# LED_Driver_and_LEDs_03.net
KiCad netlist of a schematic drawn in Altium Designer
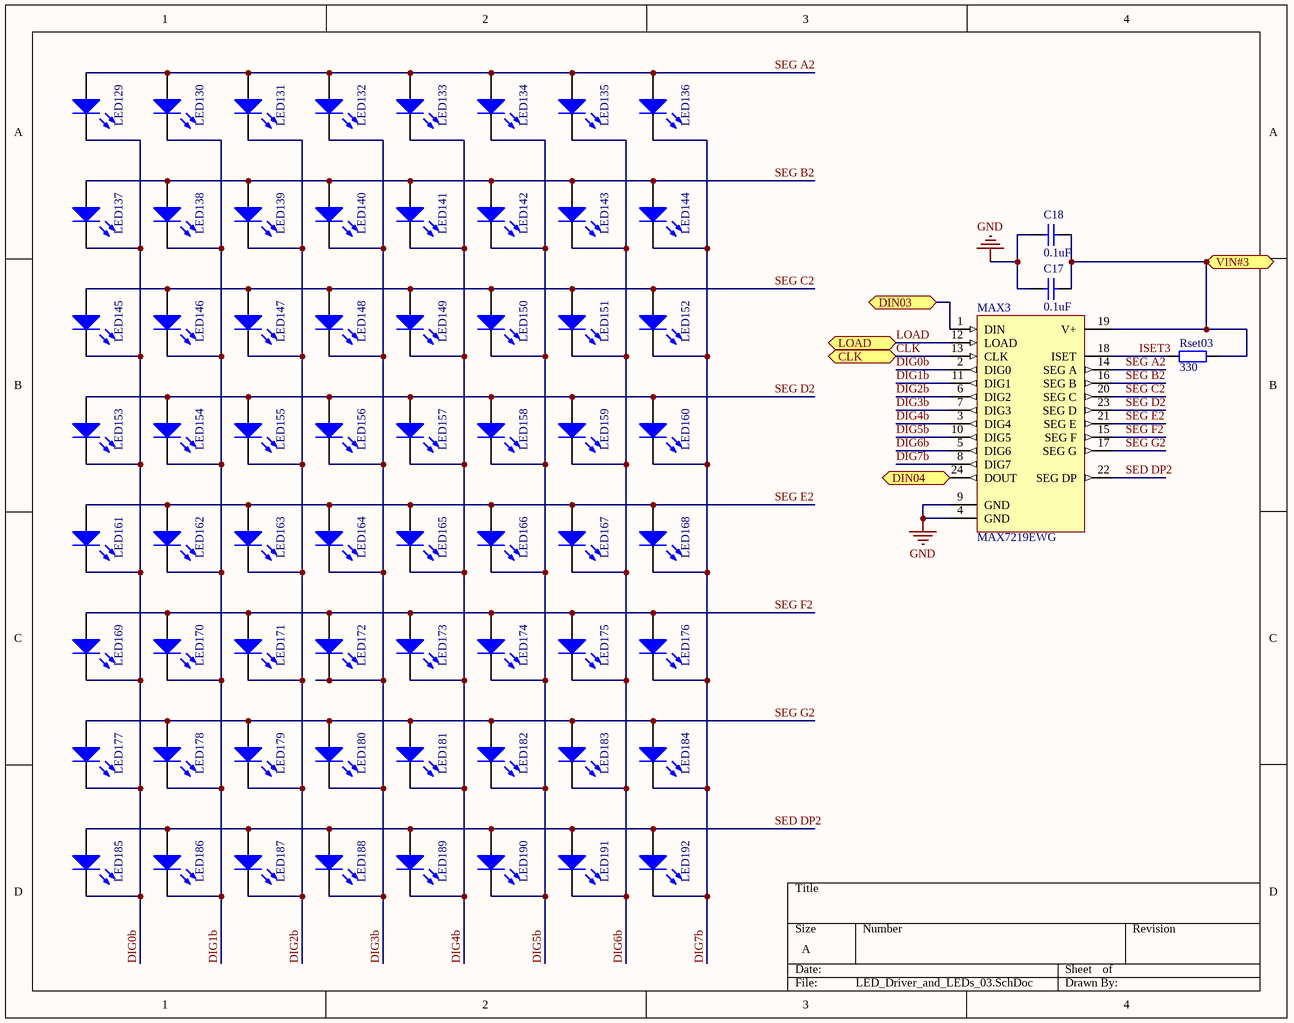
[diagram p0: LED_Driver_and_LEDs_03.SchDoc]

(export (version "E")
  (design (tool "Eeschema 10.0.6"))
  (components
    (comp (ref "C17")
      (value "0.1uF")
      (footprint "6-0805_N")
      (description "Capacitor (Semiconductor SIM Model)")
      (fields (field (name "Comment") "Cap Semi") (field (name "PUBLISHER") "Altium Limited"))
      (libsource (lib "Miscellaneous Devices") (part "Cap Semi"))
    )
    (comp (ref "C18")
      (value "0.1uF")
      (footprint "6-0805_N")
      (description "Capacitor (Semiconductor SIM Model)")
      (fields (field (name "Comment") "Cap Semi") (field (name "PUBLISHER") "Altium Limited"))
      (libsource (lib "Miscellaneous Devices") (part "Cap Semi"))
    )
    (comp (ref "LED129")
      (value "LED3")
      (footprint "3.5X2.8X1.9")
      (description "Typical BLUE SiC LED")
      (fields (field (name "PUBLISHER") "Altium Limited"))
      (libsource (lib "Miscellaneous Devices") (part "LED3"))
    )
    (comp (ref "LED130")
      (value "LED3")
      (footprint "3.5X2.8X1.9")
      (description "Typical BLUE SiC LED")
      (fields (field (name "PUBLISHER") "Altium Limited"))
      (libsource (lib "Miscellaneous Devices") (part "LED3"))
    )
    (comp (ref "LED131")
      (value "LED3")
      (footprint "3.5X2.8X1.9")
      (description "Typical BLUE SiC LED")
      (fields (field (name "PUBLISHER") "Altium Limited"))
      (libsource (lib "Miscellaneous Devices") (part "LED3"))
    )
    (comp (ref "LED132")
      (value "LED3")
      (footprint "3.5X2.8X1.9")
      (description "Typical BLUE SiC LED")
      (fields (field (name "PUBLISHER") "Altium Limited"))
      (libsource (lib "Miscellaneous Devices") (part "LED3"))
    )
    (comp (ref "LED133")
      (value "LED3")
      (footprint "3.5X2.8X1.9")
      (description "Typical BLUE SiC LED")
      (fields (field (name "PUBLISHER") "Altium Limited"))
      (libsource (lib "Miscellaneous Devices") (part "LED3"))
    )
    (comp (ref "LED134")
      (value "LED3")
      (footprint "3.5X2.8X1.9")
      (description "Typical BLUE SiC LED")
      (fields (field (name "PUBLISHER") "Altium Limited"))
      (libsource (lib "Miscellaneous Devices") (part "LED3"))
    )
    (comp (ref "LED135")
      (value "LED3")
      (footprint "3.5X2.8X1.9")
      (description "Typical BLUE SiC LED")
      (fields (field (name "PUBLISHER") "Altium Limited"))
      (libsource (lib "Miscellaneous Devices") (part "LED3"))
    )
    (comp (ref "LED136")
      (value "LED3")
      (footprint "3.5X2.8X1.9")
      (description "Typical BLUE SiC LED")
      (fields (field (name "PUBLISHER") "Altium Limited"))
      (libsource (lib "Miscellaneous Devices") (part "LED3"))
    )
    (comp (ref "LED137")
      (value "LED3")
      (footprint "3.5X2.8X1.9")
      (description "Typical BLUE SiC LED")
      (fields (field (name "PUBLISHER") "Altium Limited"))
      (libsource (lib "Miscellaneous Devices") (part "LED3"))
    )
    (comp (ref "LED138")
      (value "LED3")
      (footprint "3.5X2.8X1.9")
      (description "Typical BLUE SiC LED")
      (fields (field (name "PUBLISHER") "Altium Limited"))
      (libsource (lib "Miscellaneous Devices") (part "LED3"))
    )
    (comp (ref "LED139")
      (value "LED3")
      (footprint "3.5X2.8X1.9")
      (description "Typical BLUE SiC LED")
      (fields (field (name "PUBLISHER") "Altium Limited"))
      (libsource (lib "Miscellaneous Devices") (part "LED3"))
    )
    (comp (ref "LED140")
      (value "LED3")
      (footprint "3.5X2.8X1.9")
      (description "Typical BLUE SiC LED")
      (fields (field (name "PUBLISHER") "Altium Limited"))
      (libsource (lib "Miscellaneous Devices") (part "LED3"))
    )
    (comp (ref "LED141")
      (value "LED3")
      (footprint "3.5X2.8X1.9")
      (description "Typical BLUE SiC LED")
      (fields (field (name "PUBLISHER") "Altium Limited"))
      (libsource (lib "Miscellaneous Devices") (part "LED3"))
    )
    (comp (ref "LED142")
      (value "LED3")
      (footprint "3.5X2.8X1.9")
      (description "Typical BLUE SiC LED")
      (fields (field (name "PUBLISHER") "Altium Limited"))
      (libsource (lib "Miscellaneous Devices") (part "LED3"))
    )
    (comp (ref "LED143")
      (value "LED3")
      (footprint "3.5X2.8X1.9")
      (description "Typical BLUE SiC LED")
      (fields (field (name "PUBLISHER") "Altium Limited"))
      (libsource (lib "Miscellaneous Devices") (part "LED3"))
    )
    (comp (ref "LED144")
      (value "LED3")
      (footprint "3.5X2.8X1.9")
      (description "Typical BLUE SiC LED")
      (fields (field (name "PUBLISHER") "Altium Limited"))
      (libsource (lib "Miscellaneous Devices") (part "LED3"))
    )
    (comp (ref "LED145")
      (value "LED3")
      (footprint "3.5X2.8X1.9")
      (description "Typical BLUE SiC LED")
      (fields (field (name "PUBLISHER") "Altium Limited"))
      (libsource (lib "Miscellaneous Devices") (part "LED3"))
    )
    (comp (ref "LED146")
      (value "LED3")
      (footprint "3.5X2.8X1.9")
      (description "Typical BLUE SiC LED")
      (fields (field (name "PUBLISHER") "Altium Limited"))
      (libsource (lib "Miscellaneous Devices") (part "LED3"))
    )
    (comp (ref "LED147")
      (value "LED3")
      (footprint "3.5X2.8X1.9")
      (description "Typical BLUE SiC LED")
      (fields (field (name "PUBLISHER") "Altium Limited"))
      (libsource (lib "Miscellaneous Devices") (part "LED3"))
    )
    (comp (ref "LED148")
      (value "LED3")
      (footprint "3.5X2.8X1.9")
      (description "Typical BLUE SiC LED")
      (fields (field (name "PUBLISHER") "Altium Limited"))
      (libsource (lib "Miscellaneous Devices") (part "LED3"))
    )
    (comp (ref "LED149")
      (value "LED3")
      (footprint "3.5X2.8X1.9")
      (description "Typical BLUE SiC LED")
      (fields (field (name "PUBLISHER") "Altium Limited"))
      (libsource (lib "Miscellaneous Devices") (part "LED3"))
    )
    (comp (ref "LED150")
      (value "LED3")
      (footprint "3.5X2.8X1.9")
      (description "Typical BLUE SiC LED")
      (fields (field (name "PUBLISHER") "Altium Limited"))
      (libsource (lib "Miscellaneous Devices") (part "LED3"))
    )
    (comp (ref "LED151")
      (value "LED3")
      (footprint "3.5X2.8X1.9")
      (description "Typical BLUE SiC LED")
      (fields (field (name "PUBLISHER") "Altium Limited"))
      (libsource (lib "Miscellaneous Devices") (part "LED3"))
    )
    (comp (ref "LED152")
      (value "LED3")
      (footprint "3.5X2.8X1.9")
      (description "Typical BLUE SiC LED")
      (fields (field (name "PUBLISHER") "Altium Limited"))
      (libsource (lib "Miscellaneous Devices") (part "LED3"))
    )
    (comp (ref "LED153")
      (value "LED3")
      (footprint "3.5X2.8X1.9")
      (description "Typical BLUE SiC LED")
      (fields (field (name "PUBLISHER") "Altium Limited"))
      (libsource (lib "Miscellaneous Devices") (part "LED3"))
    )
    (comp (ref "LED154")
      (value "LED3")
      (footprint "3.5X2.8X1.9")
      (description "Typical BLUE SiC LED")
      (fields (field (name "PUBLISHER") "Altium Limited"))
      (libsource (lib "Miscellaneous Devices") (part "LED3"))
    )
    (comp (ref "LED155")
      (value "LED3")
      (footprint "3.5X2.8X1.9")
      (description "Typical BLUE SiC LED")
      (fields (field (name "PUBLISHER") "Altium Limited"))
      (libsource (lib "Miscellaneous Devices") (part "LED3"))
    )
    (comp (ref "LED156")
      (value "LED3")
      (footprint "3.5X2.8X1.9")
      (description "Typical BLUE SiC LED")
      (fields (field (name "PUBLISHER") "Altium Limited"))
      (libsource (lib "Miscellaneous Devices") (part "LED3"))
    )
    (comp (ref "LED157")
      (value "LED3")
      (footprint "3.5X2.8X1.9")
      (description "Typical BLUE SiC LED")
      (fields (field (name "PUBLISHER") "Altium Limited"))
      (libsource (lib "Miscellaneous Devices") (part "LED3"))
    )
    (comp (ref "LED158")
      (value "LED3")
      (footprint "3.5X2.8X1.9")
      (description "Typical BLUE SiC LED")
      (fields (field (name "PUBLISHER") "Altium Limited"))
      (libsource (lib "Miscellaneous Devices") (part "LED3"))
    )
    (comp (ref "LED159")
      (value "LED3")
      (footprint "3.5X2.8X1.9")
      (description "Typical BLUE SiC LED")
      (fields (field (name "PUBLISHER") "Altium Limited"))
      (libsource (lib "Miscellaneous Devices") (part "LED3"))
    )
    (comp (ref "LED160")
      (value "LED3")
      (footprint "3.5X2.8X1.9")
      (description "Typical BLUE SiC LED")
      (fields (field (name "PUBLISHER") "Altium Limited"))
      (libsource (lib "Miscellaneous Devices") (part "LED3"))
    )
    (comp (ref "LED161")
      (value "LED3")
      (footprint "3.5X2.8X1.9")
      (description "Typical BLUE SiC LED")
      (fields (field (name "PUBLISHER") "Altium Limited"))
      (libsource (lib "Miscellaneous Devices") (part "LED3"))
    )
    (comp (ref "LED162")
      (value "LED3")
      (footprint "3.5X2.8X1.9")
      (description "Typical BLUE SiC LED")
      (fields (field (name "PUBLISHER") "Altium Limited"))
      (libsource (lib "Miscellaneous Devices") (part "LED3"))
    )
    (comp (ref "LED163")
      (value "LED3")
      (footprint "3.5X2.8X1.9")
      (description "Typical BLUE SiC LED")
      (fields (field (name "PUBLISHER") "Altium Limited"))
      (libsource (lib "Miscellaneous Devices") (part "LED3"))
    )
    (comp (ref "LED164")
      (value "LED3")
      (footprint "3.5X2.8X1.9")
      (description "Typical BLUE SiC LED")
      (fields (field (name "PUBLISHER") "Altium Limited"))
      (libsource (lib "Miscellaneous Devices") (part "LED3"))
    )
    (comp (ref "LED165")
      (value "LED3")
      (footprint "3.5X2.8X1.9")
      (description "Typical BLUE SiC LED")
      (fields (field (name "PUBLISHER") "Altium Limited"))
      (libsource (lib "Miscellaneous Devices") (part "LED3"))
    )
    (comp (ref "LED166")
      (value "LED3")
      (footprint "3.5X2.8X1.9")
      (description "Typical BLUE SiC LED")
      (fields (field (name "PUBLISHER") "Altium Limited"))
      (libsource (lib "Miscellaneous Devices") (part "LED3"))
    )
    (comp (ref "LED167")
      (value "LED3")
      (footprint "3.5X2.8X1.9")
      (description "Typical BLUE SiC LED")
      (fields (field (name "PUBLISHER") "Altium Limited"))
      (libsource (lib "Miscellaneous Devices") (part "LED3"))
    )
    (comp (ref "LED168")
      (value "LED3")
      (footprint "3.5X2.8X1.9")
      (description "Typical BLUE SiC LED")
      (fields (field (name "PUBLISHER") "Altium Limited"))
      (libsource (lib "Miscellaneous Devices") (part "LED3"))
    )
    (comp (ref "LED169")
      (value "LED3")
      (footprint "3.5X2.8X1.9")
      (description "Typical BLUE SiC LED")
      (fields (field (name "PUBLISHER") "Altium Limited"))
      (libsource (lib "Miscellaneous Devices") (part "LED3"))
    )
    (comp (ref "LED170")
      (value "LED3")
      (footprint "3.5X2.8X1.9")
      (description "Typical BLUE SiC LED")
      (fields (field (name "PUBLISHER") "Altium Limited"))
      (libsource (lib "Miscellaneous Devices") (part "LED3"))
    )
    (comp (ref "LED171")
      (value "LED3")
      (footprint "3.5X2.8X1.9")
      (description "Typical BLUE SiC LED")
      (fields (field (name "PUBLISHER") "Altium Limited"))
      (libsource (lib "Miscellaneous Devices") (part "LED3"))
    )
    (comp (ref "LED172")
      (value "LED3")
      (footprint "3.5X2.8X1.9")
      (description "Typical BLUE SiC LED")
      (fields (field (name "PUBLISHER") "Altium Limited"))
      (libsource (lib "Miscellaneous Devices") (part "LED3"))
    )
    (comp (ref "LED173")
      (value "LED3")
      (footprint "3.5X2.8X1.9")
      (description "Typical BLUE SiC LED")
      (fields (field (name "PUBLISHER") "Altium Limited"))
      (libsource (lib "Miscellaneous Devices") (part "LED3"))
    )
    (comp (ref "LED174")
      (value "LED3")
      (footprint "3.5X2.8X1.9")
      (description "Typical BLUE SiC LED")
      (fields (field (name "PUBLISHER") "Altium Limited"))
      (libsource (lib "Miscellaneous Devices") (part "LED3"))
    )
    (comp (ref "LED175")
      (value "LED3")
      (footprint "3.5X2.8X1.9")
      (description "Typical BLUE SiC LED")
      (fields (field (name "PUBLISHER") "Altium Limited"))
      (libsource (lib "Miscellaneous Devices") (part "LED3"))
    )
    (comp (ref "LED176")
      (value "LED3")
      (footprint "3.5X2.8X1.9")
      (description "Typical BLUE SiC LED")
      (fields (field (name "PUBLISHER") "Altium Limited"))
      (libsource (lib "Miscellaneous Devices") (part "LED3"))
    )
    (comp (ref "LED177")
      (value "LED3")
      (footprint "3.5X2.8X1.9")
      (description "Typical BLUE SiC LED")
      (fields (field (name "PUBLISHER") "Altium Limited"))
      (libsource (lib "Miscellaneous Devices") (part "LED3"))
    )
    (comp (ref "LED178")
      (value "LED3")
      (footprint "3.5X2.8X1.9")
      (description "Typical BLUE SiC LED")
      (fields (field (name "PUBLISHER") "Altium Limited"))
      (libsource (lib "Miscellaneous Devices") (part "LED3"))
    )
    (comp (ref "LED179")
      (value "LED3")
      (footprint "3.5X2.8X1.9")
      (description "Typical BLUE SiC LED")
      (fields (field (name "PUBLISHER") "Altium Limited"))
      (libsource (lib "Miscellaneous Devices") (part "LED3"))
    )
    (comp (ref "LED180")
      (value "LED3")
      (footprint "3.5X2.8X1.9")
      (description "Typical BLUE SiC LED")
      (fields (field (name "PUBLISHER") "Altium Limited"))
      (libsource (lib "Miscellaneous Devices") (part "LED3"))
    )
    (comp (ref "LED181")
      (value "LED3")
      (footprint "3.5X2.8X1.9")
      (description "Typical BLUE SiC LED")
      (fields (field (name "PUBLISHER") "Altium Limited"))
      (libsource (lib "Miscellaneous Devices") (part "LED3"))
    )
    (comp (ref "LED182")
      (value "LED3")
      (footprint "3.5X2.8X1.9")
      (description "Typical BLUE SiC LED")
      (fields (field (name "PUBLISHER") "Altium Limited"))
      (libsource (lib "Miscellaneous Devices") (part "LED3"))
    )
    (comp (ref "LED183")
      (value "LED3")
      (footprint "3.5X2.8X1.9")
      (description "Typical BLUE SiC LED")
      (fields (field (name "PUBLISHER") "Altium Limited"))
      (libsource (lib "Miscellaneous Devices") (part "LED3"))
    )
    (comp (ref "LED184")
      (value "LED3")
      (footprint "3.5X2.8X1.9")
      (description "Typical BLUE SiC LED")
      (fields (field (name "PUBLISHER") "Altium Limited"))
      (libsource (lib "Miscellaneous Devices") (part "LED3"))
    )
    (comp (ref "LED185")
      (value "LED3")
      (footprint "3.5X2.8X1.9")
      (description "Typical BLUE SiC LED")
      (fields (field (name "PUBLISHER") "Altium Limited"))
      (libsource (lib "Miscellaneous Devices") (part "LED3"))
    )
    (comp (ref "LED186")
      (value "LED3")
      (footprint "3.5X2.8X1.9")
      (description "Typical BLUE SiC LED")
      (fields (field (name "PUBLISHER") "Altium Limited"))
      (libsource (lib "Miscellaneous Devices") (part "LED3"))
    )
    (comp (ref "LED187")
      (value "LED3")
      (footprint "3.5X2.8X1.9")
      (description "Typical BLUE SiC LED")
      (fields (field (name "PUBLISHER") "Altium Limited"))
      (libsource (lib "Miscellaneous Devices") (part "LED3"))
    )
    (comp (ref "LED188")
      (value "LED3")
      (footprint "3.5X2.8X1.9")
      (description "Typical BLUE SiC LED")
      (fields (field (name "PUBLISHER") "Altium Limited"))
      (libsource (lib "Miscellaneous Devices") (part "LED3"))
    )
    (comp (ref "LED189")
      (value "LED3")
      (footprint "3.5X2.8X1.9")
      (description "Typical BLUE SiC LED")
      (fields (field (name "PUBLISHER") "Altium Limited"))
      (libsource (lib "Miscellaneous Devices") (part "LED3"))
    )
    (comp (ref "LED190")
      (value "LED3")
      (footprint "3.5X2.8X1.9")
      (description "Typical BLUE SiC LED")
      (fields (field (name "PUBLISHER") "Altium Limited"))
      (libsource (lib "Miscellaneous Devices") (part "LED3"))
    )
    (comp (ref "LED191")
      (value "LED3")
      (footprint "3.5X2.8X1.9")
      (description "Typical BLUE SiC LED")
      (fields (field (name "PUBLISHER") "Altium Limited"))
      (libsource (lib "Miscellaneous Devices") (part "LED3"))
    )
    (comp (ref "LED192")
      (value "LED3")
      (footprint "3.5X2.8X1.9")
      (description "Typical BLUE SiC LED")
      (fields (field (name "PUBLISHER") "Altium Limited"))
      (libsource (lib "Miscellaneous Devices") (part "LED3"))
    )
    (comp (ref "MAX3")
      (value "MAX7219EWG")
      (footprint "WSO24_N")
      (description "Serially Interfaced, 8-Digit LED Display Driver")
      (fields (field (name "PUBLISHER") "Altium Limited"))
      (libsource (lib "Maxim Interface Display Driver") (part "MAX7219EWG"))
    )
    (comp (ref "Rset03")
      (value "330")
      (footprint "J1-0603")
      (description "Resistor")
      (fields (field (name "Comment") "Res2") (field (name "PUBLISHER") "Altium Limited"))
      (libsource (lib "Miscellaneous Devices") (part "Res2"))
    )
  )
  (nets
    (net (code "1") (name "/CLK") (class "Default")
      (node (ref "MAX3") (pin "13") (pinfunction "CLK_13") (pintype "input"))
    )
    (net (code "2") (name "/DIG0b") (class "Default")
      (node (ref "LED129") (pin "2") (pinfunction "K_2") (pintype "passive"))
      (node (ref "LED137") (pin "2") (pinfunction "K_2") (pintype "passive"))
      (node (ref "LED145") (pin "2") (pinfunction "K_2") (pintype "passive"))
      (node (ref "LED153") (pin "2") (pinfunction "K_2") (pintype "passive"))
      (node (ref "LED161") (pin "2") (pinfunction "K_2") (pintype "passive"))
      (node (ref "LED169") (pin "2") (pinfunction "K_2") (pintype "passive"))
      (node (ref "LED177") (pin "2") (pinfunction "K_2") (pintype "passive"))
      (node (ref "LED185") (pin "2") (pinfunction "K_2") (pintype "passive"))
      (node (ref "MAX3") (pin "2") (pinfunction "DIG0_2") (pintype "output"))
    )
    (net (code "3") (name "/DIG1b") (class "Default")
      (node (ref "LED130") (pin "2") (pinfunction "K_2") (pintype "passive"))
      (node (ref "LED138") (pin "2") (pinfunction "K_2") (pintype "passive"))
      (node (ref "LED146") (pin "2") (pinfunction "K_2") (pintype "passive"))
      (node (ref "LED154") (pin "2") (pinfunction "K_2") (pintype "passive"))
      (node (ref "LED162") (pin "2") (pinfunction "K_2") (pintype "passive"))
      (node (ref "LED170") (pin "2") (pinfunction "K_2") (pintype "passive"))
      (node (ref "LED178") (pin "2") (pinfunction "K_2") (pintype "passive"))
      (node (ref "LED186") (pin "2") (pinfunction "K_2") (pintype "passive"))
      (node (ref "MAX3") (pin "11") (pinfunction "DIG1_11") (pintype "output"))
    )
    (net (code "4") (name "/DIG2b") (class "Default")
      (node (ref "LED131") (pin "2") (pinfunction "K_2") (pintype "passive"))
      (node (ref "LED139") (pin "2") (pinfunction "K_2") (pintype "passive"))
      (node (ref "LED147") (pin "2") (pinfunction "K_2") (pintype "passive"))
      (node (ref "LED155") (pin "2") (pinfunction "K_2") (pintype "passive"))
      (node (ref "LED163") (pin "2") (pinfunction "K_2") (pintype "passive"))
      (node (ref "LED171") (pin "2") (pinfunction "K_2") (pintype "passive"))
      (node (ref "LED179") (pin "2") (pinfunction "K_2") (pintype "passive"))
      (node (ref "LED187") (pin "2") (pinfunction "K_2") (pintype "passive"))
      (node (ref "MAX3") (pin "6") (pinfunction "DIG2_6") (pintype "output"))
    )
    (net (code "5") (name "/DIG3b") (class "Default")
      (node (ref "LED132") (pin "2") (pinfunction "K_2") (pintype "passive"))
      (node (ref "LED140") (pin "2") (pinfunction "K_2") (pintype "passive"))
      (node (ref "LED148") (pin "2") (pinfunction "K_2") (pintype "passive"))
      (node (ref "LED156") (pin "2") (pinfunction "K_2") (pintype "passive"))
      (node (ref "LED164") (pin "2") (pinfunction "K_2") (pintype "passive"))
      (node (ref "LED172") (pin "2") (pinfunction "K_2") (pintype "passive"))
      (node (ref "LED180") (pin "2") (pinfunction "K_2") (pintype "passive"))
      (node (ref "LED188") (pin "2") (pinfunction "K_2") (pintype "passive"))
      (node (ref "MAX3") (pin "7") (pinfunction "DIG3_7") (pintype "output"))
    )
    (net (code "6") (name "/DIG4b") (class "Default")
      (node (ref "LED133") (pin "2") (pinfunction "K_2") (pintype "passive"))
      (node (ref "LED141") (pin "2") (pinfunction "K_2") (pintype "passive"))
      (node (ref "LED149") (pin "2") (pinfunction "K_2") (pintype "passive"))
      (node (ref "LED157") (pin "2") (pinfunction "K_2") (pintype "passive"))
      (node (ref "LED165") (pin "2") (pinfunction "K_2") (pintype "passive"))
      (node (ref "LED173") (pin "2") (pinfunction "K_2") (pintype "passive"))
      (node (ref "LED181") (pin "2") (pinfunction "K_2") (pintype "passive"))
      (node (ref "LED189") (pin "2") (pinfunction "K_2") (pintype "passive"))
      (node (ref "MAX3") (pin "3") (pinfunction "DIG4_3") (pintype "output"))
    )
    (net (code "7") (name "/DIG5b") (class "Default")
      (node (ref "LED134") (pin "2") (pinfunction "K_2") (pintype "passive"))
      (node (ref "LED142") (pin "2") (pinfunction "K_2") (pintype "passive"))
      (node (ref "LED150") (pin "2") (pinfunction "K_2") (pintype "passive"))
      (node (ref "LED158") (pin "2") (pinfunction "K_2") (pintype "passive"))
      (node (ref "LED166") (pin "2") (pinfunction "K_2") (pintype "passive"))
      (node (ref "LED174") (pin "2") (pinfunction "K_2") (pintype "passive"))
      (node (ref "LED182") (pin "2") (pinfunction "K_2") (pintype "passive"))
      (node (ref "LED190") (pin "2") (pinfunction "K_2") (pintype "passive"))
      (node (ref "MAX3") (pin "10") (pinfunction "DIG5_10") (pintype "output"))
    )
    (net (code "8") (name "/DIG6b") (class "Default")
      (node (ref "LED135") (pin "2") (pinfunction "K_2") (pintype "passive"))
      (node (ref "LED143") (pin "2") (pinfunction "K_2") (pintype "passive"))
      (node (ref "LED151") (pin "2") (pinfunction "K_2") (pintype "passive"))
      (node (ref "LED159") (pin "2") (pinfunction "K_2") (pintype "passive"))
      (node (ref "LED167") (pin "2") (pinfunction "K_2") (pintype "passive"))
      (node (ref "LED175") (pin "2") (pinfunction "K_2") (pintype "passive"))
      (node (ref "LED183") (pin "2") (pinfunction "K_2") (pintype "passive"))
      (node (ref "LED191") (pin "2") (pinfunction "K_2") (pintype "passive"))
      (node (ref "MAX3") (pin "5") (pinfunction "DIG6_5") (pintype "output"))
    )
    (net (code "9") (name "/DIG7b") (class "Default")
      (node (ref "LED136") (pin "2") (pinfunction "K_2") (pintype "passive"))
      (node (ref "LED144") (pin "2") (pinfunction "K_2") (pintype "passive"))
      (node (ref "LED152") (pin "2") (pinfunction "K_2") (pintype "passive"))
      (node (ref "LED160") (pin "2") (pinfunction "K_2") (pintype "passive"))
      (node (ref "LED168") (pin "2") (pinfunction "K_2") (pintype "passive"))
      (node (ref "LED176") (pin "2") (pinfunction "K_2") (pintype "passive"))
      (node (ref "LED184") (pin "2") (pinfunction "K_2") (pintype "passive"))
      (node (ref "LED192") (pin "2") (pinfunction "K_2") (pintype "passive"))
      (node (ref "MAX3") (pin "8") (pinfunction "DIG7_8") (pintype "output"))
    )
    (net (code "10") (name "/DIN03") (class "Default")
      (node (ref "MAX3") (pin "1") (pinfunction "DIN_1") (pintype "input"))
    )
    (net (code "11") (name "/DIN04") (class "Default")
      (node (ref "MAX3") (pin "24") (pinfunction "DOUT_24") (pintype "output"))
    )
    (net (code "12") (name "/ISET3") (class "Default")
      (node (ref "MAX3") (pin "18") (pinfunction "ISET_18") (pintype "passive"))
      (node (ref "Rset03") (pin "2") (pinfunction "2_2") (pintype "passive"))
    )
    (net (code "13") (name "/LOAD") (class "Default")
      (node (ref "MAX3") (pin "12") (pinfunction "LOAD_12") (pintype "input"))
    )
    (net (code "14") (name "/SED DP2") (class "Default")
      (node (ref "LED185") (pin "1") (pinfunction "A_1") (pintype "passive"))
      (node (ref "LED186") (pin "1") (pinfunction "A_1") (pintype "passive"))
      (node (ref "LED187") (pin "1") (pinfunction "A_1") (pintype "passive"))
      (node (ref "LED188") (pin "1") (pinfunction "A_1") (pintype "passive"))
      (node (ref "LED189") (pin "1") (pinfunction "A_1") (pintype "passive"))
      (node (ref "LED190") (pin "1") (pinfunction "A_1") (pintype "passive"))
      (node (ref "LED191") (pin "1") (pinfunction "A_1") (pintype "passive"))
      (node (ref "LED192") (pin "1") (pinfunction "A_1") (pintype "passive"))
      (node (ref "MAX3") (pin "22") (pinfunction "SEG_DP_22") (pintype "output"))
    )
    (net (code "15") (name "/SEG A2") (class "Default")
      (node (ref "LED129") (pin "1") (pinfunction "A_1") (pintype "passive"))
      (node (ref "LED130") (pin "1") (pinfunction "A_1") (pintype "passive"))
      (node (ref "LED131") (pin "1") (pinfunction "A_1") (pintype "passive"))
      (node (ref "LED132") (pin "1") (pinfunction "A_1") (pintype "passive"))
      (node (ref "LED133") (pin "1") (pinfunction "A_1") (pintype "passive"))
      (node (ref "LED134") (pin "1") (pinfunction "A_1") (pintype "passive"))
      (node (ref "LED135") (pin "1") (pinfunction "A_1") (pintype "passive"))
      (node (ref "LED136") (pin "1") (pinfunction "A_1") (pintype "passive"))
      (node (ref "MAX3") (pin "14") (pinfunction "SEG_A_14") (pintype "output"))
    )
    (net (code "16") (name "/SEG B2") (class "Default")
      (node (ref "LED137") (pin "1") (pinfunction "A_1") (pintype "passive"))
      (node (ref "LED138") (pin "1") (pinfunction "A_1") (pintype "passive"))
      (node (ref "LED139") (pin "1") (pinfunction "A_1") (pintype "passive"))
      (node (ref "LED140") (pin "1") (pinfunction "A_1") (pintype "passive"))
      (node (ref "LED141") (pin "1") (pinfunction "A_1") (pintype "passive"))
      (node (ref "LED142") (pin "1") (pinfunction "A_1") (pintype "passive"))
      (node (ref "LED143") (pin "1") (pinfunction "A_1") (pintype "passive"))
      (node (ref "LED144") (pin "1") (pinfunction "A_1") (pintype "passive"))
      (node (ref "MAX3") (pin "16") (pinfunction "SEG_B_16") (pintype "output"))
    )
    (net (code "17") (name "/SEG C2") (class "Default")
      (node (ref "LED145") (pin "1") (pinfunction "A_1") (pintype "passive"))
      (node (ref "LED146") (pin "1") (pinfunction "A_1") (pintype "passive"))
      (node (ref "LED147") (pin "1") (pinfunction "A_1") (pintype "passive"))
      (node (ref "LED148") (pin "1") (pinfunction "A_1") (pintype "passive"))
      (node (ref "LED149") (pin "1") (pinfunction "A_1") (pintype "passive"))
      (node (ref "LED150") (pin "1") (pinfunction "A_1") (pintype "passive"))
      (node (ref "LED151") (pin "1") (pinfunction "A_1") (pintype "passive"))
      (node (ref "LED152") (pin "1") (pinfunction "A_1") (pintype "passive"))
      (node (ref "MAX3") (pin "20") (pinfunction "SEG_C_20") (pintype "output"))
    )
    (net (code "18") (name "/SEG D2") (class "Default")
      (node (ref "LED153") (pin "1") (pinfunction "A_1") (pintype "passive"))
      (node (ref "LED154") (pin "1") (pinfunction "A_1") (pintype "passive"))
      (node (ref "LED155") (pin "1") (pinfunction "A_1") (pintype "passive"))
      (node (ref "LED156") (pin "1") (pinfunction "A_1") (pintype "passive"))
      (node (ref "LED157") (pin "1") (pinfunction "A_1") (pintype "passive"))
      (node (ref "LED158") (pin "1") (pinfunction "A_1") (pintype "passive"))
      (node (ref "LED159") (pin "1") (pinfunction "A_1") (pintype "passive"))
      (node (ref "LED160") (pin "1") (pinfunction "A_1") (pintype "passive"))
      (node (ref "MAX3") (pin "23") (pinfunction "SEG_D_23") (pintype "output"))
    )
    (net (code "19") (name "/SEG E2") (class "Default")
      (node (ref "LED161") (pin "1") (pinfunction "A_1") (pintype "passive"))
      (node (ref "LED162") (pin "1") (pinfunction "A_1") (pintype "passive"))
      (node (ref "LED163") (pin "1") (pinfunction "A_1") (pintype "passive"))
      (node (ref "LED164") (pin "1") (pinfunction "A_1") (pintype "passive"))
      (node (ref "LED165") (pin "1") (pinfunction "A_1") (pintype "passive"))
      (node (ref "LED166") (pin "1") (pinfunction "A_1") (pintype "passive"))
      (node (ref "LED167") (pin "1") (pinfunction "A_1") (pintype "passive"))
      (node (ref "LED168") (pin "1") (pinfunction "A_1") (pintype "passive"))
      (node (ref "MAX3") (pin "21") (pinfunction "SEG_E_21") (pintype "output"))
    )
    (net (code "20") (name "/SEG F2") (class "Default")
      (node (ref "LED169") (pin "1") (pinfunction "A_1") (pintype "passive"))
      (node (ref "LED170") (pin "1") (pinfunction "A_1") (pintype "passive"))
      (node (ref "LED171") (pin "1") (pinfunction "A_1") (pintype "passive"))
      (node (ref "LED172") (pin "1") (pinfunction "A_1") (pintype "passive"))
      (node (ref "LED173") (pin "1") (pinfunction "A_1") (pintype "passive"))
      (node (ref "LED174") (pin "1") (pinfunction "A_1") (pintype "passive"))
      (node (ref "LED175") (pin "1") (pinfunction "A_1") (pintype "passive"))
      (node (ref "LED176") (pin "1") (pinfunction "A_1") (pintype "passive"))
      (node (ref "MAX3") (pin "15") (pinfunction "SEG_F_15") (pintype "output"))
    )
    (net (code "21") (name "/SEG G2") (class "Default")
      (node (ref "LED177") (pin "1") (pinfunction "A_1") (pintype "passive"))
      (node (ref "LED178") (pin "1") (pinfunction "A_1") (pintype "passive"))
      (node (ref "LED179") (pin "1") (pinfunction "A_1") (pintype "passive"))
      (node (ref "LED180") (pin "1") (pinfunction "A_1") (pintype "passive"))
      (node (ref "LED181") (pin "1") (pinfunction "A_1") (pintype "passive"))
      (node (ref "LED182") (pin "1") (pinfunction "A_1") (pintype "passive"))
      (node (ref "LED183") (pin "1") (pinfunction "A_1") (pintype "passive"))
      (node (ref "LED184") (pin "1") (pinfunction "A_1") (pintype "passive"))
      (node (ref "MAX3") (pin "17") (pinfunction "SEG_G_17") (pintype "output"))
    )
    (net (code "22") (name "/VIN#3") (class "Default")
      (node (ref "C17") (pin "1") (pinfunction "1_1") (pintype "passive"))
      (node (ref "C18") (pin "1") (pinfunction "1_1") (pintype "passive"))
      (node (ref "MAX3") (pin "19") (pinfunction "V+_19") (pintype "power_in"))
      (node (ref "Rset03") (pin "1") (pinfunction "1_1") (pintype "passive"))
    )
    (net (code "23") (name "GND") (class "Default")
      (node (ref "C17") (pin "2") (pinfunction "2_2") (pintype "passive"))
      (node (ref "C18") (pin "2") (pinfunction "2_2") (pintype "passive"))
      (node (ref "MAX3") (pin "4") (pinfunction "GND_4") (pintype "power_in"))
      (node (ref "MAX3") (pin "9") (pinfunction "GND_9") (pintype "power_in"))
    )
  )
)
